# MCU.net
KiCad netlist of a schematic drawn in Altium Designer
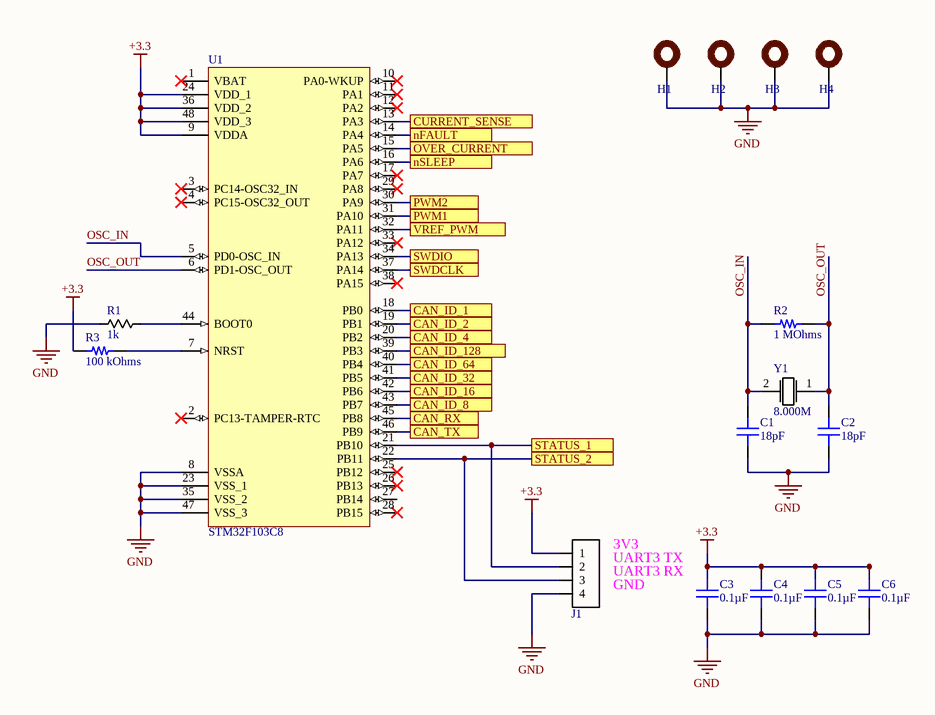
[diagram p0: MCU.SchDoc]

(export (version "E")
  (design (tool "Eeschema 10.0.6"))
  (components
    (comp (ref "C1")
      (value "18pF")
      (footprint "CAP 0603_1608")
      (description "CAP CER 18PF 50V C0G/NP0 0603")
      (fields (field (name "PART NUMBER") "C0603X180J5GACTU") (field (name "MANUFACTURER") "KEMET"))
      (libsource (lib "Celestial Altium Library - altium_library") (part "Capacitor"))
    )
    (comp (ref "C2")
      (value "18pF")
      (footprint "CAP 0603_1608")
      (description "CAP CER 18PF 50V C0G/NP0 0603")
      (fields (field (name "PART NUMBER") "C0603X180J5GACTU") (field (name "MANUFACTURER") "KEMET"))
      (libsource (lib "Celestial Altium Library - altium_library") (part "Capacitor"))
    )
    (comp (ref "C3")
      (value "0.1µF")
      (footprint "CAP 0805_2012")
      (description "CAP CER 0805 0.1UF 50V X7R")
      (fields (field (name "PART NUMBER") "C0805X104K5RAC3316") (field (name "MANUFACTURER") "KEMET"))
      (libsource (lib "Celestial Altium Library - altium_library") (part "Capacitor"))
    )
    (comp (ref "C4")
      (value "0.1µF")
      (footprint "CAP 0805_2012")
      (description "CAP CER 0805 0.1UF 50V X7R")
      (fields (field (name "PART NUMBER") "C0805X104K5RAC3316") (field (name "MANUFACTURER") "KEMET"))
      (libsource (lib "Celestial Altium Library - altium_library") (part "Capacitor"))
    )
    (comp (ref "C5")
      (value "0.1µF")
      (footprint "CAP 0805_2012")
      (description "CAP CER 0805 0.1UF 50V X7R")
      (fields (field (name "PART NUMBER") "C0805X104K5RAC3316") (field (name "MANUFACTURER") "KEMET"))
      (libsource (lib "Celestial Altium Library - altium_library") (part "Capacitor"))
    )
    (comp (ref "C6")
      (value "0.1µF")
      (footprint "CAP 0805_2012")
      (description "CAP CER 0805 0.1UF 50V X7R")
      (fields (field (name "PART NUMBER") "C0805X104K5RAC3316") (field (name "MANUFACTURER") "KEMET"))
      (libsource (lib "Celestial Altium Library - altium_library") (part "Capacitor"))
    )
    (comp (ref "H1")
      (value "mounting_hole_0")
      (footprint "#8-32_SOCKET_HEAD")
      (description "#8-32 Mounting Hole for Socket Head Cap Screw")
      (fields (field (name "PART NUMBER") "MISC-00027"))
      (libsource (lib "Misc") (part "mounting_hole_0"))
    )
    (comp (ref "H2")
      (value "mounting_hole_0")
      (footprint "#8-32_SOCKET_HEAD")
      (description "#8-32 Mounting Hole for Socket Head Cap Screw")
      (fields (field (name "PART NUMBER") "MISC-00027"))
      (libsource (lib "Misc") (part "mounting_hole_0"))
    )
    (comp (ref "H3")
      (value "mounting_hole_0")
      (footprint "#8-32_SOCKET_HEAD")
      (description "#8-32 Mounting Hole for Socket Head Cap Screw")
      (fields (field (name "PART NUMBER") "MISC-00027"))
      (libsource (lib "Misc") (part "mounting_hole_0"))
    )
    (comp (ref "H4")
      (value "mounting_hole_0")
      (footprint "#8-32_SOCKET_HEAD")
      (description "#8-32 Mounting Hole for Socket Head Cap Screw")
      (fields (field (name "PART NUMBER") "MISC-00027"))
      (libsource (lib "Misc") (part "mounting_hole_0"))
    )
    (comp (ref "J1")
      (value "conn-4x1_0")
      (footprint "HDDR_4x1_0")
      (description "Header 4x1, 0.1\"")
      (fields (field (name "PART NUMBER") "CONN-00029"))
      (libsource (lib "Connectors$") (part "CONN-00029"))
    )
    (comp (ref "R1")
      (value "1k")
      (footprint "chip_0805")
      (description "RES SMD 1K OHM 1% 1/8W 0805")
      (fields (field (name "PART NUMBER") "RES-00361") (field (name "TOLERANCE") "1%"))
      (libsource (lib "Resistors$") (part "RES-00361"))
    )
    (comp (ref "R2")
      (value "1 MOhms")
      (footprint "RES 0603_1608")
      (description "RES SMD 1M OHM 1% 1/4W 0603")
      (fields (field (name "PART NUMBER") "RCS06031M00FKEA") (field (name "MANUFACTURER") "Vishay Dale"))
      (libsource (lib "Celestial Altium Library - altium_library") (part "Resistor"))
    )
    (comp (ref "R3")
      (value "100 kOhms")
      (footprint "RES 0603_1608")
      (description "RES SMD 100K OHM 1% 1/4W 0603")
      (fields (field (name "PART NUMBER") "CRCW0603100KFKEAHP") (field (name "MANUFACTURER") "Vishay Dale"))
      (libsource (lib "Celestial Altium Library - altium_library") (part "Resistor"))
    )
    (comp (ref "U1")
      (value "STM32F103C8")
      (footprint "LQFP48_0")
      (description "STM32 M3, LQFP-48")
      (fields (field (name "PART NUMBER") "UCTRL-00008") (field (name "MANUFACTURER") "ST"))
      (libsource (lib "Microcontrollers") (part "STM32F103C8"))
    )
    (comp (ref "Y1")
      (value "osc_xtal_2p_0")
      (footprint "ABLS_AT49_OSC")
      (description "XTAL, 8MHz, 18pF, 20ppm")
      (fields
        (field (name "TOLERANCE") "20ppm")
        (field (name "FREQUENCY") "8.000M")
        (field (name "PART NUMBER") "OSC-00002")
      )
      (libsource (lib "Oscillators") (part "osc_xtal_2p_0"))
    )
  )
  (nets
    (net (code "1") (name "+3.3") (class "Default")
      (node (ref "C3") (pin "2") (pinfunction "2_2") (pintype "passive"))
      (node (ref "C4") (pin "2") (pinfunction "2_2") (pintype "passive"))
      (node (ref "C5") (pin "2") (pinfunction "2_2") (pintype "passive"))
      (node (ref "C6") (pin "2") (pinfunction "2_2") (pintype "passive"))
      (node (ref "J1") (pin "1") (pinfunction "1_1") (pintype "passive"))
      (node (ref "R3") (pin "1") (pinfunction "1_1") (pintype "passive"))
      (node (ref "U1") (pin "24") (pinfunction "VDD_1_24") (pintype "power_in"))
      (node (ref "U1") (pin "36") (pinfunction "VDD_2_36") (pintype "power_in"))
      (node (ref "U1") (pin "48") (pinfunction "VDD_3_48") (pintype "power_in"))
      (node (ref "U1") (pin "9") (pinfunction "VDDA_9") (pintype "power_in"))
    )
    (net (code "2") (name "/CAN_ID_1") (class "Default")
      (node (ref "U1") (pin "18") (pinfunction "PB0_18") (pintype "bidirectional"))
    )
    (net (code "3") (name "/CAN_ID_2") (class "Default")
      (node (ref "U1") (pin "19") (pinfunction "PB1_19") (pintype "bidirectional"))
    )
    (net (code "4") (name "/CAN_ID_4") (class "Default")
      (node (ref "U1") (pin "20") (pinfunction "PB2_20") (pintype "bidirectional"))
    )
    (net (code "5") (name "/CAN_ID_8") (class "Default")
      (node (ref "U1") (pin "43") (pinfunction "PB7_43") (pintype "bidirectional"))
    )
    (net (code "6") (name "/CAN_ID_16") (class "Default")
      (node (ref "U1") (pin "42") (pinfunction "PB6_42") (pintype "bidirectional"))
    )
    (net (code "7") (name "/CAN_ID_32") (class "Default")
      (node (ref "U1") (pin "41") (pinfunction "PB5_41") (pintype "bidirectional"))
    )
    (net (code "8") (name "/CAN_ID_64") (class "Default")
      (node (ref "U1") (pin "40") (pinfunction "PB4_40") (pintype "bidirectional"))
    )
    (net (code "9") (name "/CAN_ID_128") (class "Default")
      (node (ref "U1") (pin "39") (pinfunction "PB3_39") (pintype "bidirectional"))
    )
    (net (code "10") (name "/CAN_RX") (class "Default")
      (node (ref "U1") (pin "45") (pinfunction "PB8_45") (pintype "bidirectional"))
    )
    (net (code "11") (name "/CAN_TX") (class "Default")
      (node (ref "U1") (pin "46") (pinfunction "PB9_46") (pintype "bidirectional"))
    )
    (net (code "12") (name "/CURRENT_SENSE") (class "Default")
      (node (ref "U1") (pin "13") (pinfunction "PA3_13") (pintype "bidirectional"))
    )
    (net (code "13") (name "/OSC_IN") (class "Default")
      (node (ref "C1") (pin "2") (pinfunction "2_2") (pintype "passive"))
      (node (ref "R2") (pin "1") (pinfunction "1_1") (pintype "passive"))
      (node (ref "U1") (pin "5") (pinfunction "PD0-OSC_IN_5") (pintype "bidirectional"))
      (node (ref "Y1") (pin "2") (pinfunction "20_2") (pintype "passive"))
    )
    (net (code "14") (name "/OSC_OUT") (class "Default")
      (node (ref "C2") (pin "2") (pinfunction "2_2") (pintype "passive"))
      (node (ref "R2") (pin "2") (pinfunction "2_2") (pintype "passive"))
      (node (ref "U1") (pin "6") (pinfunction "PD1-OSC_OUT_6") (pintype "bidirectional"))
      (node (ref "Y1") (pin "1") (pinfunction "20_1") (pintype "passive"))
    )
    (net (code "15") (name "/OVER_CURRENT") (class "Default")
      (node (ref "U1") (pin "15") (pinfunction "PA5_15") (pintype "bidirectional"))
    )
    (net (code "16") (name "/PWM1") (class "Default")
      (node (ref "U1") (pin "31") (pinfunction "PA10_31") (pintype "bidirectional"))
    )
    (net (code "17") (name "/PWM2") (class "Default")
      (node (ref "U1") (pin "30") (pinfunction "PA9_30") (pintype "bidirectional"))
    )
    (net (code "18") (name "/STATUS_1") (class "Default")
      (node (ref "J1") (pin "2") (pinfunction "2_2") (pintype "passive"))
      (node (ref "U1") (pin "21") (pinfunction "PB10_21") (pintype "bidirectional"))
    )
    (net (code "19") (name "/STATUS_2") (class "Default")
      (node (ref "J1") (pin "3") (pinfunction "3_3") (pintype "passive"))
      (node (ref "U1") (pin "22") (pinfunction "PB11_22") (pintype "bidirectional"))
    )
    (net (code "20") (name "/SWDCLK") (class "Default")
      (node (ref "U1") (pin "37") (pinfunction "PA14_37") (pintype "bidirectional"))
    )
    (net (code "21") (name "/SWDIO") (class "Default")
      (node (ref "U1") (pin "34") (pinfunction "PA13_34") (pintype "bidirectional"))
    )
    (net (code "22") (name "/VREF_PWM") (class "Default")
      (node (ref "U1") (pin "32") (pinfunction "PA11_32") (pintype "bidirectional"))
    )
    (net (code "23") (name "/nFAULT") (class "Default")
      (node (ref "U1") (pin "14") (pinfunction "PA4_14") (pintype "bidirectional"))
    )
    (net (code "24") (name "/nSLEEP") (class "Default")
      (node (ref "U1") (pin "16") (pinfunction "PA6_16") (pintype "bidirectional"))
    )
    (net (code "25") (name "GND") (class "Default")
      (node (ref "C1") (pin "1") (pinfunction "1_1") (pintype "passive"))
      (node (ref "C2") (pin "1") (pinfunction "1_1") (pintype "passive"))
      (node (ref "C3") (pin "1") (pinfunction "1_1") (pintype "passive"))
      (node (ref "C4") (pin "1") (pinfunction "1_1") (pintype "passive"))
      (node (ref "C5") (pin "1") (pinfunction "1_1") (pintype "passive"))
      (node (ref "C6") (pin "1") (pinfunction "1_1") (pintype "passive"))
      (node (ref "H1") (pin "0") (pinfunction "A_0") (pintype "passive"))
      (node (ref "H2") (pin "0") (pinfunction "A_0") (pintype "passive"))
      (node (ref "H3") (pin "0") (pinfunction "A_0") (pintype "passive"))
      (node (ref "H4") (pin "0") (pinfunction "A_0") (pintype "passive"))
      (node (ref "J1") (pin "4") (pinfunction "4_4") (pintype "passive"))
      (node (ref "R1") (pin "1") (pinfunction "1_1") (pintype "passive"))
      (node (ref "U1") (pin "23") (pinfunction "VSS_1_23") (pintype "power_in"))
      (node (ref "U1") (pin "35") (pinfunction "VSS_2_35") (pintype "power_in"))
      (node (ref "U1") (pin "47") (pinfunction "VSS_3_47") (pintype "power_in"))
      (node (ref "U1") (pin "8") (pinfunction "VSSA_8") (pintype "power_in"))
    )
    (net (code "26") (name "Net-(U1-BOOT0)") (class "Default")
      (node (ref "R1") (pin "2") (pinfunction "2_2") (pintype "passive"))
      (node (ref "U1") (pin "44") (pinfunction "BOOT0_44") (pintype "input"))
    )
    (net (code "27") (name "Net-(U1-NRST)") (class "Default")
      (node (ref "R3") (pin "2") (pinfunction "2_2") (pintype "passive"))
      (node (ref "U1") (pin "7") (pinfunction "NRST_7") (pintype "input"))
    )
    (net (code "28") (name "unconnected-(U1-PA0-WKUP-Pad10)") (class "Default")
      (node (ref "U1") (pin "10") (pinfunction "PA0-WKUP_10") (pintype "bidirectional+no_connect"))
    )
    (net (code "29") (name "unconnected-(U1-PA1-Pad11)") (class "Default")
      (node (ref "U1") (pin "11") (pinfunction "PA1_11") (pintype "bidirectional+no_connect"))
    )
    (net (code "30") (name "unconnected-(U1-PA2-Pad12)") (class "Default")
      (node (ref "U1") (pin "12") (pinfunction "PA2_12") (pintype "bidirectional+no_connect"))
    )
    (net (code "31") (name "unconnected-(U1-PA7-Pad17)") (class "Default")
      (node (ref "U1") (pin "17") (pinfunction "PA7_17") (pintype "bidirectional+no_connect"))
    )
    (net (code "32") (name "unconnected-(U1-PA8-Pad29)") (class "Default")
      (node (ref "U1") (pin "29") (pinfunction "PA8_29") (pintype "bidirectional+no_connect"))
    )
    (net (code "33") (name "unconnected-(U1-PA12-Pad33)") (class "Default")
      (node (ref "U1") (pin "33") (pinfunction "PA12_33") (pintype "bidirectional+no_connect"))
    )
    (net (code "34") (name "unconnected-(U1-PA15-Pad38)") (class "Default")
      (node (ref "U1") (pin "38") (pinfunction "PA15_38") (pintype "bidirectional+no_connect"))
    )
    (net (code "35") (name "unconnected-(U1-PB12-Pad25)") (class "Default")
      (node (ref "U1") (pin "25") (pinfunction "PB12_25") (pintype "bidirectional+no_connect"))
    )
    (net (code "36") (name "unconnected-(U1-PB13-Pad26)") (class "Default")
      (node (ref "U1") (pin "26") (pinfunction "PB13_26") (pintype "bidirectional+no_connect"))
    )
    (net (code "37") (name "unconnected-(U1-PB14-Pad27)") (class "Default")
      (node (ref "U1") (pin "27") (pinfunction "PB14_27") (pintype "bidirectional"))
    )
    (net (code "38") (name "unconnected-(U1-PB15-Pad28)") (class "Default")
      (node (ref "U1") (pin "28") (pinfunction "PB15_28") (pintype "bidirectional+no_connect"))
    )
    (net (code "39") (name "unconnected-(U1-PC13-TAMPER-RTC-Pad2)") (class "Default")
      (node (ref "U1") (pin "2") (pinfunction "PC13-TAMPER-RTC_2") (pintype "bidirectional+no_connect"))
    )
    (net (code "40") (name "unconnected-(U1-PC14-OSC32_IN-Pad3)") (class "Default")
      (node (ref "U1") (pin "3") (pinfunction "PC14-OSC32_IN_3") (pintype "bidirectional+no_connect"))
    )
    (net (code "41") (name "unconnected-(U1-PC15-OSC32_OUT-Pad4)") (class "Default")
      (node (ref "U1") (pin "4") (pinfunction "PC15-OSC32_OUT_4") (pintype "bidirectional+no_connect"))
    )
    (net (code "42") (name "unconnected-(U1-VBAT-Pad1)") (class "Default")
      (node (ref "U1") (pin "1") (pinfunction "VBAT_1") (pintype "passive+no_connect"))
    )
  )
)
